# uSD_Card.net
KiCad netlist of a schematic drawn in Altium Designer
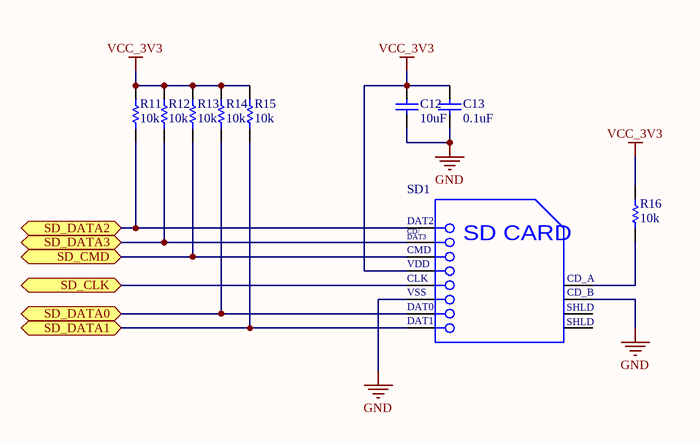
[diagram p0: uSD_Card.SchDoc]

(export (version "E")
  (design (tool "Eeschema 10.0.6"))
  (components
    (comp (ref "C12")
      (value "10uF")
      (footprint "0805_C_S")
      (description "Capacitor")
      (fields (field (name "PUBLISHER") "Altium Limited"))
      (libsource (lib "Miscellaneous Devices") (part "Cap"))
    )
    (comp (ref "C13")
      (value "0.1uF")
      (footprint "0805_C_S")
      (description "Capacitor")
      (fields (field (name "PUBLISHER") "Altium Limited"))
      (libsource (lib "Miscellaneous Devices") (part "Cap"))
    )
    (comp (ref "R11")
      (value "10k")
      (footprint "0805_R_S")
      (description "Resistor")
      (fields (field (name "PUBLISHER") "Altium Limited"))
      (libsource (lib "Miscellaneous Devices") (part "Res1"))
    )
    (comp (ref "R12")
      (value "10k")
      (footprint "0805_R_S")
      (description "Resistor")
      (fields (field (name "PUBLISHER") "Altium Limited"))
      (libsource (lib "Miscellaneous Devices") (part "Res1"))
    )
    (comp (ref "R13")
      (value "10k")
      (footprint "0805_R_S")
      (description "Resistor")
      (fields (field (name "PUBLISHER") "Altium Limited"))
      (libsource (lib "Miscellaneous Devices") (part "Res1"))
    )
    (comp (ref "R14")
      (value "10k")
      (footprint "0805_R_S")
      (description "Resistor")
      (fields (field (name "PUBLISHER") "Altium Limited"))
      (libsource (lib "Miscellaneous Devices") (part "Res1"))
    )
    (comp (ref "R15")
      (value "10k")
      (footprint "0805_R_S")
      (description "Resistor")
      (fields (field (name "PUBLISHER") "Altium Limited"))
      (libsource (lib "Miscellaneous Devices") (part "Res1"))
    )
    (comp (ref "R16")
      (value "10k")
      (footprint "0805_R_S")
      (description "Resistor")
      (fields (field (name "PUBLISHER") "Altium Limited"))
      (libsource (lib "Miscellaneous Devices") (part "Res1"))
    )
    (comp (ref "SD1")
      (value "104031-0811")
      (footprint "MOLX-104031-0811_V")
      (description "Micro SD Card, RA, -25 to 85 degC, 8-Pin SMD, RoHS, Tape and Reel")
      (fields (field (name "MANUFACTURER") "Molex"))
      (libsource (lib "Altium Content Vault") (part "CN-SD-8-2SW-2S"))
    )
  )
  (nets
    (net (code "1") (name "/SD_CLK") (class "Default")
      (node (ref "SD1") (pin "5") (pinfunction "CLK_5") (pintype "passive"))
    )
    (net (code "2") (name "/SD_CMD") (class "Default")
      (node (ref "R13") (pin "2") (pinfunction "2_2") (pintype "passive"))
      (node (ref "SD1") (pin "3") (pinfunction "VSS1_3") (pintype "passive"))
    )
    (net (code "3") (name "/SD_DATA0") (class "Default")
      (node (ref "R14") (pin "2") (pinfunction "2_2") (pintype "passive"))
      (node (ref "SD1") (pin "7") (pinfunction "DAT0_7") (pintype "passive"))
    )
    (net (code "4") (name "/SD_DATA1") (class "Default")
      (node (ref "R15") (pin "2") (pinfunction "2_2") (pintype "passive"))
      (node (ref "SD1") (pin "8") (pinfunction "DAT1_8") (pintype "passive"))
    )
    (net (code "5") (name "/SD_DATA2") (class "Default")
      (node (ref "R11") (pin "2") (pinfunction "2_2") (pintype "passive"))
      (node (ref "SD1") (pin "1") (pinfunction "CD/DAT3_1") (pintype "passive"))
    )
    (net (code "6") (name "/SD_DATA3") (class "Default")
      (node (ref "R12") (pin "2") (pinfunction "2_2") (pintype "passive"))
      (node (ref "SD1") (pin "2") (pinfunction "CMD_2") (pintype "passive"))
    )
    (net (code "7") (name "GND") (class "Default")
      (node (ref "C12") (pin "1") (pinfunction "1_1") (pintype "passive"))
      (node (ref "C13") (pin "1") (pinfunction "1_1") (pintype "passive"))
      (node (ref "SD1") (pin "10") (pinfunction "CD_B_10") (pintype "passive"))
      (node (ref "SD1") (pin "6") (pinfunction "VSS2_6") (pintype "passive"))
    )
    (net (code "8") (name "Net-(SD1-CD_A)") (class "Default")
      (node (ref "R16") (pin "2") (pinfunction "2_2") (pintype "passive"))
      (node (ref "SD1") (pin "9") (pinfunction "CD_A_9") (pintype "passive"))
    )
    (net (code "9") (name "VCC_3V3") (class "Default")
      (node (ref "C12") (pin "2") (pinfunction "2_2") (pintype "passive"))
      (node (ref "C13") (pin "2") (pinfunction "2_2") (pintype "passive"))
      (node (ref "R11") (pin "1") (pinfunction "1_1") (pintype "passive"))
      (node (ref "R12") (pin "1") (pinfunction "1_1") (pintype "passive"))
      (node (ref "R13") (pin "1") (pinfunction "1_1") (pintype "passive"))
      (node (ref "R14") (pin "1") (pinfunction "1_1") (pintype "passive"))
      (node (ref "R15") (pin "1") (pinfunction "1_1") (pintype "passive"))
      (node (ref "R16") (pin "1") (pinfunction "1_1") (pintype "passive"))
      (node (ref "SD1") (pin "4") (pinfunction "VDD_4") (pintype "passive"))
    )
    (net (code "10") (name "unconnected-(SD1-SHLD1-Pad11)") (class "Default")
      (node (ref "SD1") (pin "11") (pinfunction "SHLD1_11") (pintype "passive"))
    )
    (net (code "11") (name "unconnected-(SD1-SHLD2-Pad12)") (class "Default")
      (node (ref "SD1") (pin "12") (pinfunction "SHLD2_12") (pintype "passive"))
    )
  )
)
